# ai_charger_lipo.net
KiCad netlist of a schematic drawn in EAGLE
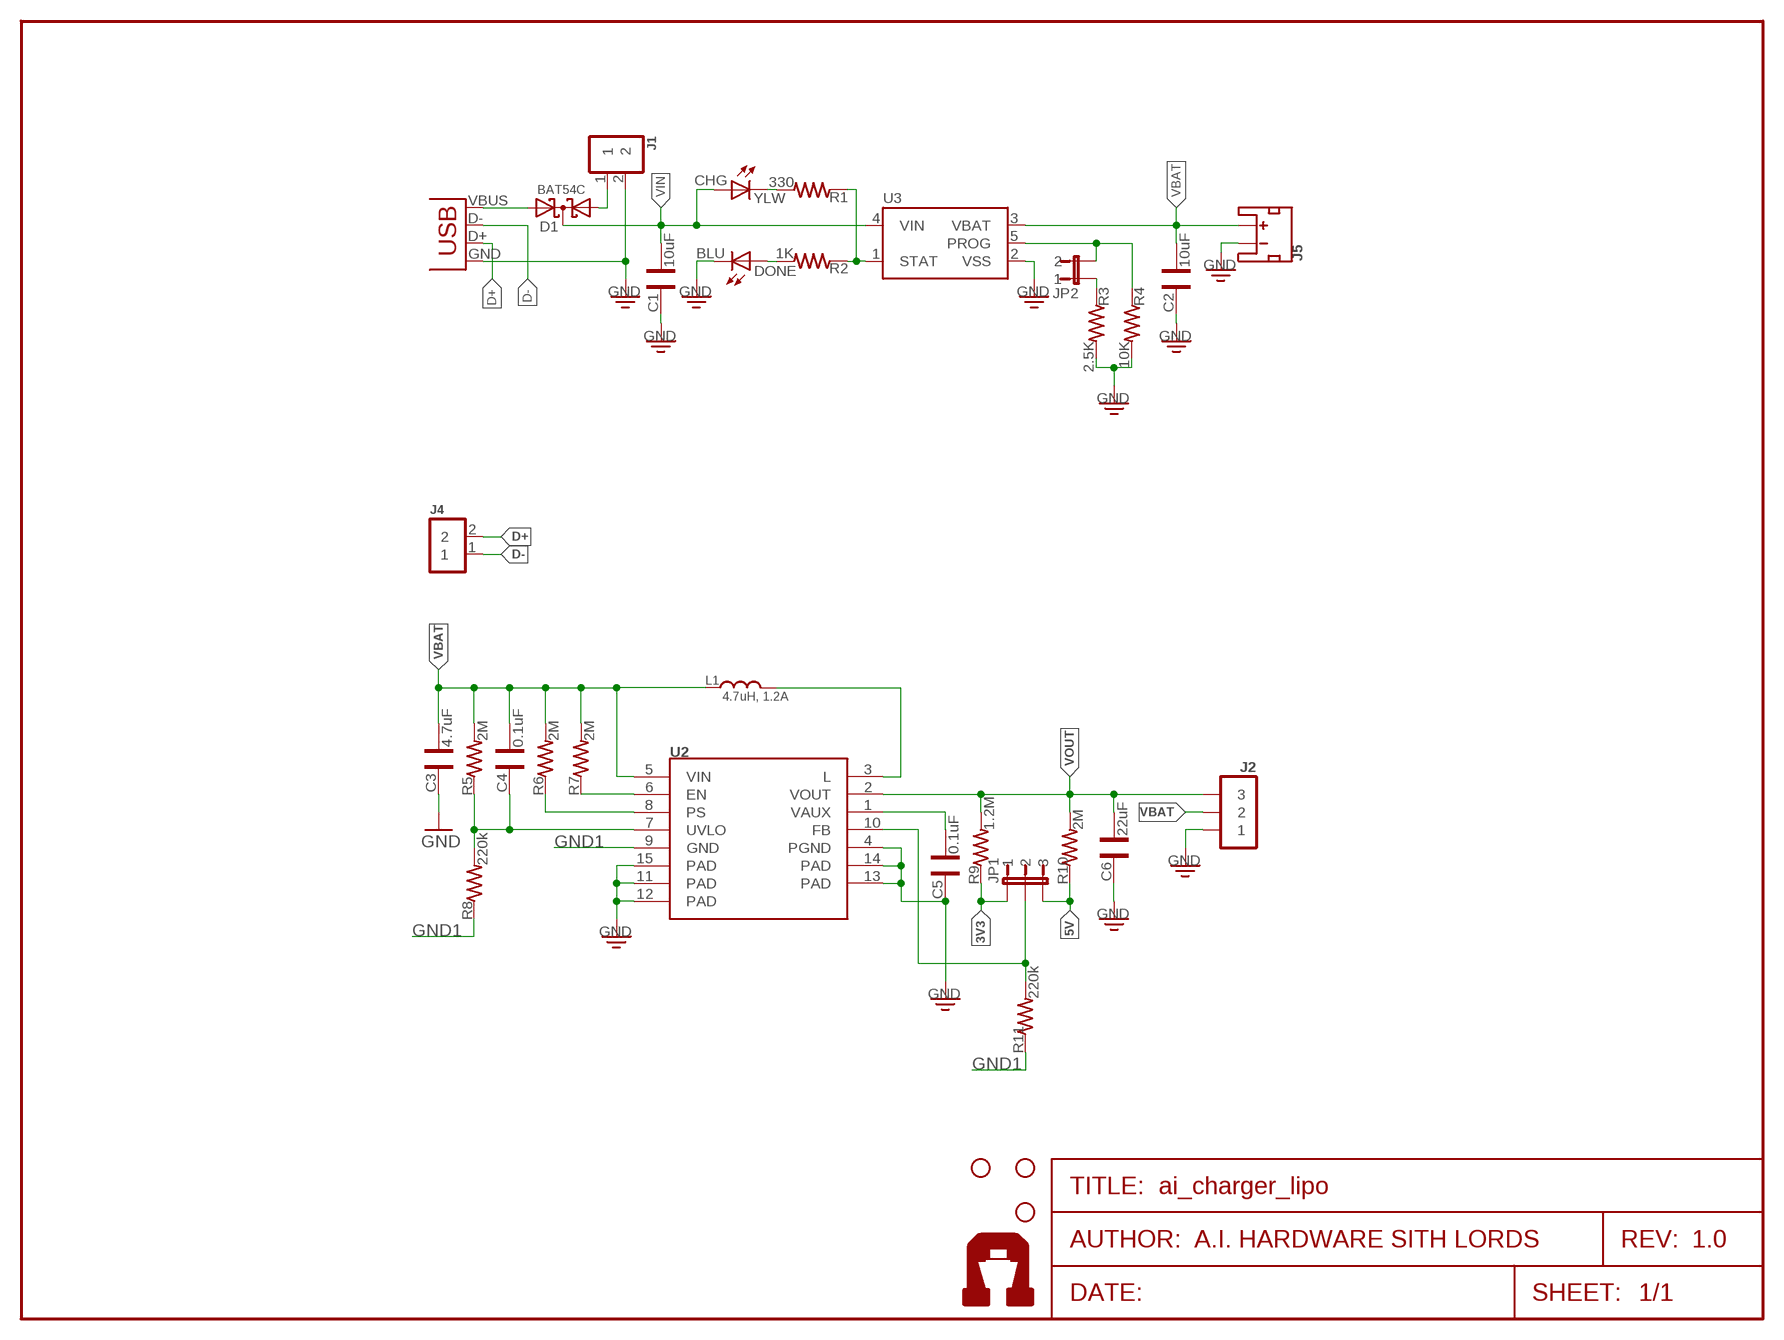
[diagram p0: schematic, sheet 1]

(export (version "E")
  (design (tool "Eeschema 10.0.6"))
  (components
    (comp (ref "C1")
      (value "10uF")
      (footprint "eagle-import:CAP-0603")
      (libsource (lib "eagle-import") (part "CAP0603"))
    )
    (comp (ref "C2")
      (value "10uF")
      (footprint "eagle-import:CAP-0603")
      (libsource (lib "eagle-import") (part "CAP0603"))
    )
    (comp (ref "C3")
      (value "4.7uF")
      (footprint "eagle-import:CAP-0603")
      (libsource (lib "eagle-import") (part "CAP0603"))
    )
    (comp (ref "C4")
      (value "0.1uF")
      (footprint "eagle-import:CAP-0603")
      (libsource (lib "eagle-import") (part "CAP0603"))
    )
    (comp (ref "C5")
      (value "0.1uF")
      (footprint "eagle-import:CAP-0603")
      (libsource (lib "eagle-import") (part "CAP0603"))
    )
    (comp (ref "C6")
      (value "22uF")
      (footprint "eagle-import:CAP-0603")
      (libsource (lib "eagle-import") (part "CAP0603"))
    )
    (comp (ref "CHG")
      (value "YLW")
      (footprint "eagle-import:LED-0603")
      (libsource (lib "eagle-import") (part "LED0603"))
    )
    (comp (ref "D1")
      (value "BAT54C")
      (footprint "eagle-import:SOT-23")
      (libsource (lib "eagle-import") (part "BAT54C"))
    )
    (comp (ref "DONE")
      (value "BLU")
      (footprint "eagle-import:LED-0603")
      (libsource (lib "eagle-import") (part "LED0603"))
    )
    (comp (ref "J1")
      (value "1X02ST")
      (footprint "eagle-import:1X02-ST")
      (libsource (lib "eagle-import") (part "1X02ST"))
    )
    (comp (ref "J2")
      (value "1X03NOFIRST")
      (footprint "eagle-import:1X03-NOFIRST")
      (libsource (lib "eagle-import") (part "1X03NOFIRST"))
    )
    (comp (ref "J4")
      (value "1X02NOFIRST")
      (footprint "eagle-import:1X02-NOFIRST")
      (libsource (lib "eagle-import") (part "1X02NOFIRST"))
    )
    (comp (ref "J5")
      (value "JST-2-MALE")
      (footprint "eagle-import:JST-2-SMD")
      (libsource (lib "eagle-import") (part "JST-2-MALE"))
    )
    (comp (ref "JP1")
      (value "1X03-PJNOFIRST")
      (footprint "eagle-import:1X03-NOFIRST")
      (libsource (lib "eagle-import") (part "1X03-PJNOFIRST"))
    )
    (comp (ref "JP2")
      (value "1X02-PJNOFIRST")
      (footprint "eagle-import:1X02-NOFIRST")
      (libsource (lib "eagle-import") (part "1X02-PJNOFIRST"))
    )
    (comp (ref "L1")
      (value "4.7uH, 1.2A")
      (footprint "eagle-import:IND-0603")
      (libsource (lib "eagle-import") (part "IND0603"))
    )
    (comp (ref "R1")
      (value "330")
      (footprint "eagle-import:RES-0603")
      (libsource (lib "eagle-import") (part "RES0603"))
    )
    (comp (ref "R2")
      (value "1K")
      (footprint "eagle-import:RES-0603")
      (libsource (lib "eagle-import") (part "RES0603"))
    )
    (comp (ref "R3")
      (value "2.5K")
      (footprint "eagle-import:RES-0603")
      (libsource (lib "eagle-import") (part "RES0603"))
    )
    (comp (ref "R4")
      (value "10K")
      (footprint "eagle-import:RES-0603")
      (libsource (lib "eagle-import") (part "RES0603"))
    )
    (comp (ref "R5")
      (value "2M")
      (footprint "eagle-import:RES-0603")
      (libsource (lib "eagle-import") (part "RES0603"))
    )
    (comp (ref "R6")
      (value "2M")
      (footprint "eagle-import:RES-0603")
      (libsource (lib "eagle-import") (part "RES0603"))
    )
    (comp (ref "R7")
      (value "2M")
      (footprint "eagle-import:RES-0603")
      (libsource (lib "eagle-import") (part "RES0603"))
    )
    (comp (ref "R8")
      (value "220k")
      (footprint "eagle-import:RES-0603")
      (libsource (lib "eagle-import") (part "RES0603"))
    )
    (comp (ref "R9")
      (value "1.2M")
      (footprint "eagle-import:RES-0603")
      (libsource (lib "eagle-import") (part "RES0603"))
    )
    (comp (ref "R10")
      (value "2M")
      (footprint "eagle-import:RES-0603")
      (libsource (lib "eagle-import") (part "RES0603"))
    )
    (comp (ref "R11")
      (value "220k")
      (footprint "eagle-import:RES-0603")
      (libsource (lib "eagle-import") (part "RES0603"))
    )
    (comp (ref "STANDOFF1")
      (value "STAND-OFF")
      (footprint "eagle-import:STAND-OFF")
      (libsource (lib "eagle-import") (part "STAND-OFF"))
    )
    (comp (ref "STANDOFF2")
      (value "STAND-OFF")
      (footprint "eagle-import:STAND-OFF")
      (libsource (lib "eagle-import") (part "STAND-OFF"))
    )
    (comp (ref "STANDOFF3")
      (value "STAND-OFF")
      (footprint "eagle-import:STAND-OFF")
      (libsource (lib "eagle-import") (part "STAND-OFF"))
    )
    (comp (ref "U$1")
      (value "AI-LOGOXS")
      (footprint "eagle-import:AI-LOGO-XS")
      (libsource (lib "eagle-import") (part "AI-LOGOXS"))
    )
    (comp (ref "U$2")
      (value "AI-LOGOXS")
      (footprint "eagle-import:AI-LOGO-XS")
      (libsource (lib "eagle-import") (part "AI-LOGOXS"))
    )
    (comp (ref "U2")
      (value "TPS61200")
      (footprint "eagle-import:QFN-10-PAD")
      (libsource (lib "eagle-import") (part "TPS61200"))
    )
    (comp (ref "U3")
      (value "MCP73831")
      (footprint "eagle-import:SOT23-5")
      (libsource (lib "eagle-import") (part "MCP73831"))
    )
    (comp (ref "X2")
      (value "USBMICROB-TH")
      (footprint "eagle-import:USB-MICROB-TH")
      (libsource (lib "eagle-import") (part "USBMICROB-TH"))
    )
  )
  (nets
    (net (code "1") (name "/GND1") (class "Default")
      (node (ref "R11") (pin "1") (pinfunction "1_1") (pintype "passive"))
      (node (ref "R8") (pin "1") (pinfunction "1_1") (pintype "passive"))
      (node (ref "U2") (pin "9") (pinfunction "GND_9") (pintype "power_in"))
    )
    (net (code "2") (name "3V3") (class "Default")
      (node (ref "JP1") (pin "1") (pinfunction "1_1") (pintype "passive"))
      (node (ref "R9") (pin "1") (pinfunction "1_1") (pintype "passive"))
    )
    (net (code "3") (name "5V") (class "Default")
      (node (ref "JP1") (pin "3") (pinfunction "3_3") (pintype "passive"))
      (node (ref "R10") (pin "1") (pinfunction "1_1") (pintype "passive"))
    )
    (net (code "4") (name "D+") (class "Default")
      (node (ref "J4") (pin "2") (pinfunction "2_2") (pintype "bidirectional"))
      (node (ref "X2") (pin "D+") (pinfunction "D+_D+") (pintype "bidirectional"))
    )
    (net (code "5") (name "D-") (class "Default")
      (node (ref "J4") (pin "1") (pinfunction "1_1") (pintype "bidirectional"))
      (node (ref "X2") (pin "D-") (pinfunction "D-_D-") (pintype "bidirectional"))
    )
    (net (code "6") (name "GND") (class "Default")
      (node (ref "C1") (pin "2") (pinfunction "2_2") (pintype "passive"))
      (node (ref "C2") (pin "2") (pinfunction "2_2") (pintype "passive"))
      (node (ref "C3") (pin "2") (pinfunction "2_2") (pintype "passive"))
      (node (ref "C5") (pin "2") (pinfunction "2_2") (pintype "passive"))
      (node (ref "C6") (pin "2") (pinfunction "2_2") (pintype "passive"))
      (node (ref "DONE") (pin "C") (pinfunction "C_C") (pintype "passive"))
      (node (ref "J1") (pin "2") (pinfunction "2_2") (pintype "bidirectional"))
      (node (ref "J2") (pin "1") (pinfunction "1_1") (pintype "bidirectional"))
      (node (ref "J5") (pin "2") (pinfunction "-_2") (pintype "power_in"))
      (node (ref "R3") (pin "2") (pinfunction "2_2") (pintype "passive"))
      (node (ref "R4") (pin "2") (pinfunction "2_2") (pintype "passive"))
      (node (ref "U2") (pin "11") (pinfunction "PAD_11") (pintype "power_in"))
      (node (ref "U2") (pin "12") (pinfunction "PAD_12") (pintype "power_in"))
      (node (ref "U2") (pin "13") (pinfunction "PAD_13") (pintype "power_in"))
      (node (ref "U2") (pin "14") (pinfunction "PAD_14") (pintype "power_in"))
      (node (ref "U2") (pin "15") (pinfunction "PAD_15") (pintype "power_in"))
      (node (ref "U2") (pin "4") (pinfunction "PGND_4") (pintype "power_in"))
      (node (ref "U3") (pin "2") (pinfunction "VSS_2") (pintype "power_in"))
      (node (ref "X2") (pin "GND") (pinfunction "GND_GND") (pintype "bidirectional"))
    )
    (net (code "7") (name "Net-(CHG-PadC)") (class "Default")
      (node (ref "CHG") (pin "C") (pinfunction "C_C") (pintype "passive"))
      (node (ref "R1") (pin "2") (pinfunction "2_2") (pintype "passive"))
    )
    (net (code "8") (name "Net-(D1-A1)") (class "Default")
      (node (ref "D1") (pin "1") (pinfunction "A1_1") (pintype "passive"))
      (node (ref "J1") (pin "1") (pinfunction "1_1") (pintype "bidirectional"))
    )
    (net (code "9") (name "Net-(D1-A2)") (class "Default")
      (node (ref "D1") (pin "2") (pinfunction "A2_2") (pintype "passive"))
      (node (ref "X2") (pin "VBUS") (pinfunction "VBUS_VBUS") (pintype "bidirectional"))
    )
    (net (code "10") (name "Net-(DONE-PadA)") (class "Default")
      (node (ref "DONE") (pin "A") (pinfunction "A_A") (pintype "passive"))
      (node (ref "R2") (pin "2") (pinfunction "2_2") (pintype "passive"))
    )
    (net (code "11") (name "Net-(JP2-Pad1)") (class "Default")
      (node (ref "JP2") (pin "1") (pinfunction "1_1") (pintype "passive"))
      (node (ref "R3") (pin "1") (pinfunction "1_1") (pintype "passive"))
    )
    (net (code "12") (name "Net-(U2-EN)") (class "Default")
      (node (ref "R7") (pin "1") (pinfunction "1_1") (pintype "passive"))
      (node (ref "U2") (pin "6") (pinfunction "EN_6") (pintype "input"))
    )
    (net (code "13") (name "Net-(U2-FB)") (class "Default")
      (node (ref "JP1") (pin "2") (pinfunction "2_2") (pintype "passive"))
      (node (ref "R11") (pin "2") (pinfunction "2_2") (pintype "passive"))
      (node (ref "U2") (pin "10") (pinfunction "FB_10") (pintype "passive"))
    )
    (net (code "14") (name "Net-(U2-L)") (class "Default")
      (node (ref "L1") (pin "1") (pinfunction "1_1") (pintype "passive"))
      (node (ref "U2") (pin "3") (pinfunction "L_3") (pintype "passive"))
    )
    (net (code "15") (name "Net-(U2-PS)") (class "Default")
      (node (ref "R6") (pin "1") (pinfunction "1_1") (pintype "passive"))
      (node (ref "U2") (pin "8") (pinfunction "PS_8") (pintype "input"))
    )
    (net (code "16") (name "Net-(U2-UVLO)") (class "Default")
      (node (ref "C4") (pin "2") (pinfunction "2_2") (pintype "passive"))
      (node (ref "R5") (pin "1") (pinfunction "1_1") (pintype "passive"))
      (node (ref "R8") (pin "2") (pinfunction "2_2") (pintype "passive"))
      (node (ref "U2") (pin "7") (pinfunction "UVLO_7") (pintype "passive"))
    )
    (net (code "17") (name "Net-(U2-VAUX)") (class "Default")
      (node (ref "C5") (pin "1") (pinfunction "1_1") (pintype "passive"))
      (node (ref "U2") (pin "1") (pinfunction "VAUX_1") (pintype "passive"))
    )
    (net (code "18") (name "Net-(U3-PROG)") (class "Default")
      (node (ref "JP2") (pin "2") (pinfunction "2_2") (pintype "passive"))
      (node (ref "R4") (pin "1") (pinfunction "1_1") (pintype "passive"))
      (node (ref "U3") (pin "5") (pinfunction "PROG_5") (pintype "input"))
    )
    (net (code "19") (name "Net-(U3-STAT)") (class "Default")
      (node (ref "R1") (pin "1") (pinfunction "1_1") (pintype "passive"))
      (node (ref "R2") (pin "1") (pinfunction "1_1") (pintype "passive"))
      (node (ref "U3") (pin "1") (pinfunction "STAT_1") (pintype "output"))
    )
    (net (code "20") (name "VBAT") (class "Default")
      (node (ref "C2") (pin "1") (pinfunction "1_1") (pintype "passive"))
      (node (ref "C3") (pin "1") (pinfunction "1_1") (pintype "passive"))
      (node (ref "C4") (pin "1") (pinfunction "1_1") (pintype "passive"))
      (node (ref "J2") (pin "2") (pinfunction "2_2") (pintype "bidirectional"))
      (node (ref "J5") (pin "1") (pinfunction "+_1") (pintype "power_in"))
      (node (ref "L1") (pin "2") (pinfunction "2_2") (pintype "passive"))
      (node (ref "R5") (pin "2") (pinfunction "2_2") (pintype "passive"))
      (node (ref "R6") (pin "2") (pinfunction "2_2") (pintype "passive"))
      (node (ref "R7") (pin "2") (pinfunction "2_2") (pintype "passive"))
      (node (ref "U2") (pin "5") (pinfunction "VIN_5") (pintype "power_in"))
      (node (ref "U3") (pin "3") (pinfunction "VBAT_3") (pintype "power_in"))
    )
    (net (code "21") (name "VIN") (class "Default")
      (node (ref "C1") (pin "1") (pinfunction "1_1") (pintype "passive"))
      (node (ref "CHG") (pin "A") (pinfunction "A_A") (pintype "passive"))
      (node (ref "D1") (pin "3") (pinfunction "CC_3") (pintype "passive"))
      (node (ref "U3") (pin "4") (pinfunction "VIN_4") (pintype "power_in"))
    )
    (net (code "22") (name "VOUT") (class "Default")
      (node (ref "C6") (pin "1") (pinfunction "1_1") (pintype "passive"))
      (node (ref "J2") (pin "3") (pinfunction "3_3") (pintype "bidirectional"))
      (node (ref "R10") (pin "2") (pinfunction "2_2") (pintype "passive"))
      (node (ref "R9") (pin "2") (pinfunction "2_2") (pintype "passive"))
      (node (ref "U2") (pin "2") (pinfunction "VOUT_2") (pintype "passive"))
    )
  )
)
